# Boost-to-12V_test.net
KiCad netlist of a schematic drawn in Altium Designer
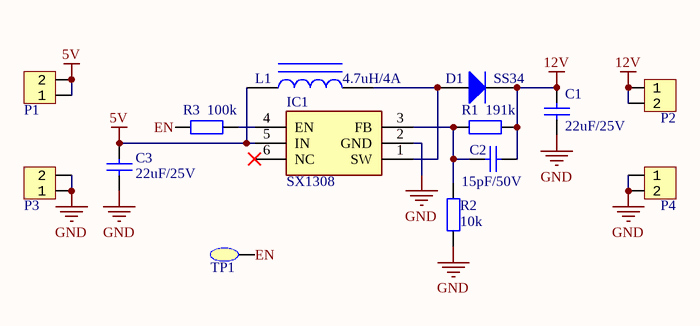
[diagram p0: Boost-to-12V_test.SchDoc]

(export (version "E")
  (design (tool "Eeschema 10.0.6"))
  (components
    (comp (ref "C1")
      (value "22uF/25V")
      (footprint "CAP-0603")
      (description "X7R")
      (libsource (lib "Power_Lib_Altium") (part "CAP"))
    )
    (comp (ref "C2")
      (value "15pF/50V")
      (footprint "CAP-0603")
      (description "NPO")
      (libsource (lib "Power_Lib_Altium") (part "CAP"))
    )
    (comp (ref "C3")
      (value "22uF/25V")
      (footprint "CAP-0603")
      (description "X7R")
      (libsource (lib "Power_Lib_Altium") (part "CAP"))
    )
    (comp (ref "D1")
      (value "SS34")
      (footprint "DO-214AC_SMA")
      (description "肖特基二极管")
      (libsource (lib "Power_Lib_Altium") (part "DIODE"))
    )
    (comp (ref "IC1")
      (value "SX1308")
      (footprint "SOT-23-6")
      (description "集成升压芯片")
      (libsource (lib "Power_Lib_Altium") (part "SX1308"))
    )
    (comp (ref "L1")
      (value "4.7uH/4A")
      (footprint "SMD_7.3x7.3x4.2mm")
      (description "电感")
      (libsource (lib "Power_Lib_Altium") (part "INDUCTOR"))
    )
    (comp (ref "P1")
      (value "HDR1x2_2.54")
      (footprint "HDR1X2_2.54_180")
      (description "Header")
      (libsource (lib "Power_Lib_Altium") (part "HDR1x2_2.54"))
    )
    (comp (ref "P2")
      (value "HDR1x2_2.54")
      (footprint "HDR1X2_2.54_180")
      (description "Header")
      (libsource (lib "") (part "HDR1x2_2.54_1"))
    )
    (comp (ref "P3")
      (value "HDR1x2_2.54")
      (footprint "HDR1X2_2.54_180")
      (description "Header")
      (libsource (lib "Power_Lib_Altium") (part "HDR1x2_2.54"))
    )
    (comp (ref "P4")
      (value "HDR1x2_2.54")
      (footprint "HDR1X2_2.54_180")
      (description "Header")
      (libsource (lib "") (part "HDR1x2_2.54_1"))
    )
    (comp (ref "R1")
      (value "191k")
      (footprint "R-0603")
      (description "贴片电阻")
      (libsource (lib "Power_Lib_Altium") (part "RES"))
    )
    (comp (ref "R2")
      (value "10k")
      (footprint "R-0603")
      (description "贴片电阻")
      (libsource (lib "") (part "RES_1"))
    )
    (comp (ref "R3")
      (value "100k")
      (footprint "R-0603")
      (description "贴片电阻")
      (libsource (lib "Power_Lib_Altium") (part "RES"))
    )
    (comp (ref "TP1")
      (value "TestPoint")
      (footprint "TestPoint")
      (description "测试点")
      (libsource (lib "Power_Lib_Altium") (part "TestPoint"))
    )
  )
  (nets
    (net (code "1") (name "/EN") (class "Default")
      (node (ref "R3") (pin "1") (pinfunction "1_1") (pintype "passive"))
      (node (ref "TP1") (pin "1") (pinfunction "1_1") (pintype "passive"))
    )
    (net (code "2") (name "5V") (class "Default")
      (node (ref "C3") (pin "2") (pinfunction "2_2") (pintype "passive"))
      (node (ref "IC1") (pin "5") (pinfunction "IN_5") (pintype "passive"))
      (node (ref "L1") (pin "1") (pinfunction "1_1") (pintype "passive"))
      (node (ref "P1") (pin "1") (pinfunction "1_1") (pintype "passive"))
      (node (ref "P1") (pin "2") (pinfunction "2_2") (pintype "passive"))
    )
    (net (code "3") (name "12V") (class "Default")
      (node (ref "C1") (pin "2") (pinfunction "2_2") (pintype "passive"))
      (node (ref "C2") (pin "2") (pinfunction "2_2") (pintype "passive"))
      (node (ref "D1") (pin "2") (pinfunction "K_2") (pintype "passive"))
      (node (ref "P2") (pin "1") (pinfunction "1_1") (pintype "passive"))
      (node (ref "P2") (pin "2") (pinfunction "2_2") (pintype "passive"))
      (node (ref "R1") (pin "2") (pinfunction "2_2") (pintype "passive"))
    )
    (net (code "4") (name "GND") (class "Default")
      (node (ref "C1") (pin "1") (pinfunction "1_1") (pintype "passive"))
      (node (ref "C3") (pin "1") (pinfunction "1_1") (pintype "passive"))
      (node (ref "IC1") (pin "2") (pinfunction "GND_2") (pintype "passive"))
      (node (ref "P3") (pin "1") (pinfunction "1_1") (pintype "passive"))
      (node (ref "P3") (pin "2") (pinfunction "2_2") (pintype "passive"))
      (node (ref "P4") (pin "1") (pinfunction "1_1") (pintype "passive"))
      (node (ref "P4") (pin "2") (pinfunction "2_2") (pintype "passive"))
      (node (ref "R2") (pin "1") (pinfunction "1_1") (pintype "passive"))
    )
    (net (code "5") (name "Net-(D1-A)") (class "Default")
      (node (ref "D1") (pin "1") (pinfunction "A_1") (pintype "passive"))
      (node (ref "IC1") (pin "1") (pinfunction "SW_1") (pintype "passive"))
      (node (ref "L1") (pin "2") (pinfunction "2_2") (pintype "passive"))
    )
    (net (code "6") (name "Net-(IC1-EN)") (class "Default")
      (node (ref "IC1") (pin "4") (pinfunction "EN_4") (pintype "passive"))
      (node (ref "R3") (pin "2") (pinfunction "2_2") (pintype "passive"))
    )
    (net (code "7") (name "Net-(IC1-FB)") (class "Default")
      (node (ref "C2") (pin "1") (pinfunction "1_1") (pintype "passive"))
      (node (ref "IC1") (pin "3") (pinfunction "FB_3") (pintype "passive"))
      (node (ref "R1") (pin "1") (pinfunction "1_1") (pintype "passive"))
      (node (ref "R2") (pin "2") (pinfunction "2_2") (pintype "passive"))
    )
    (net (code "8") (name "unconnected-(IC1-NC-Pad6)") (class "Default")
      (node (ref "IC1") (pin "6") (pinfunction "NC_6") (pintype "passive+no_connect"))
    )
  )
)
